# sch_the-weather-gian_2026-05-13.net
KiCad netlist of a schematic drawn in EasyEDA
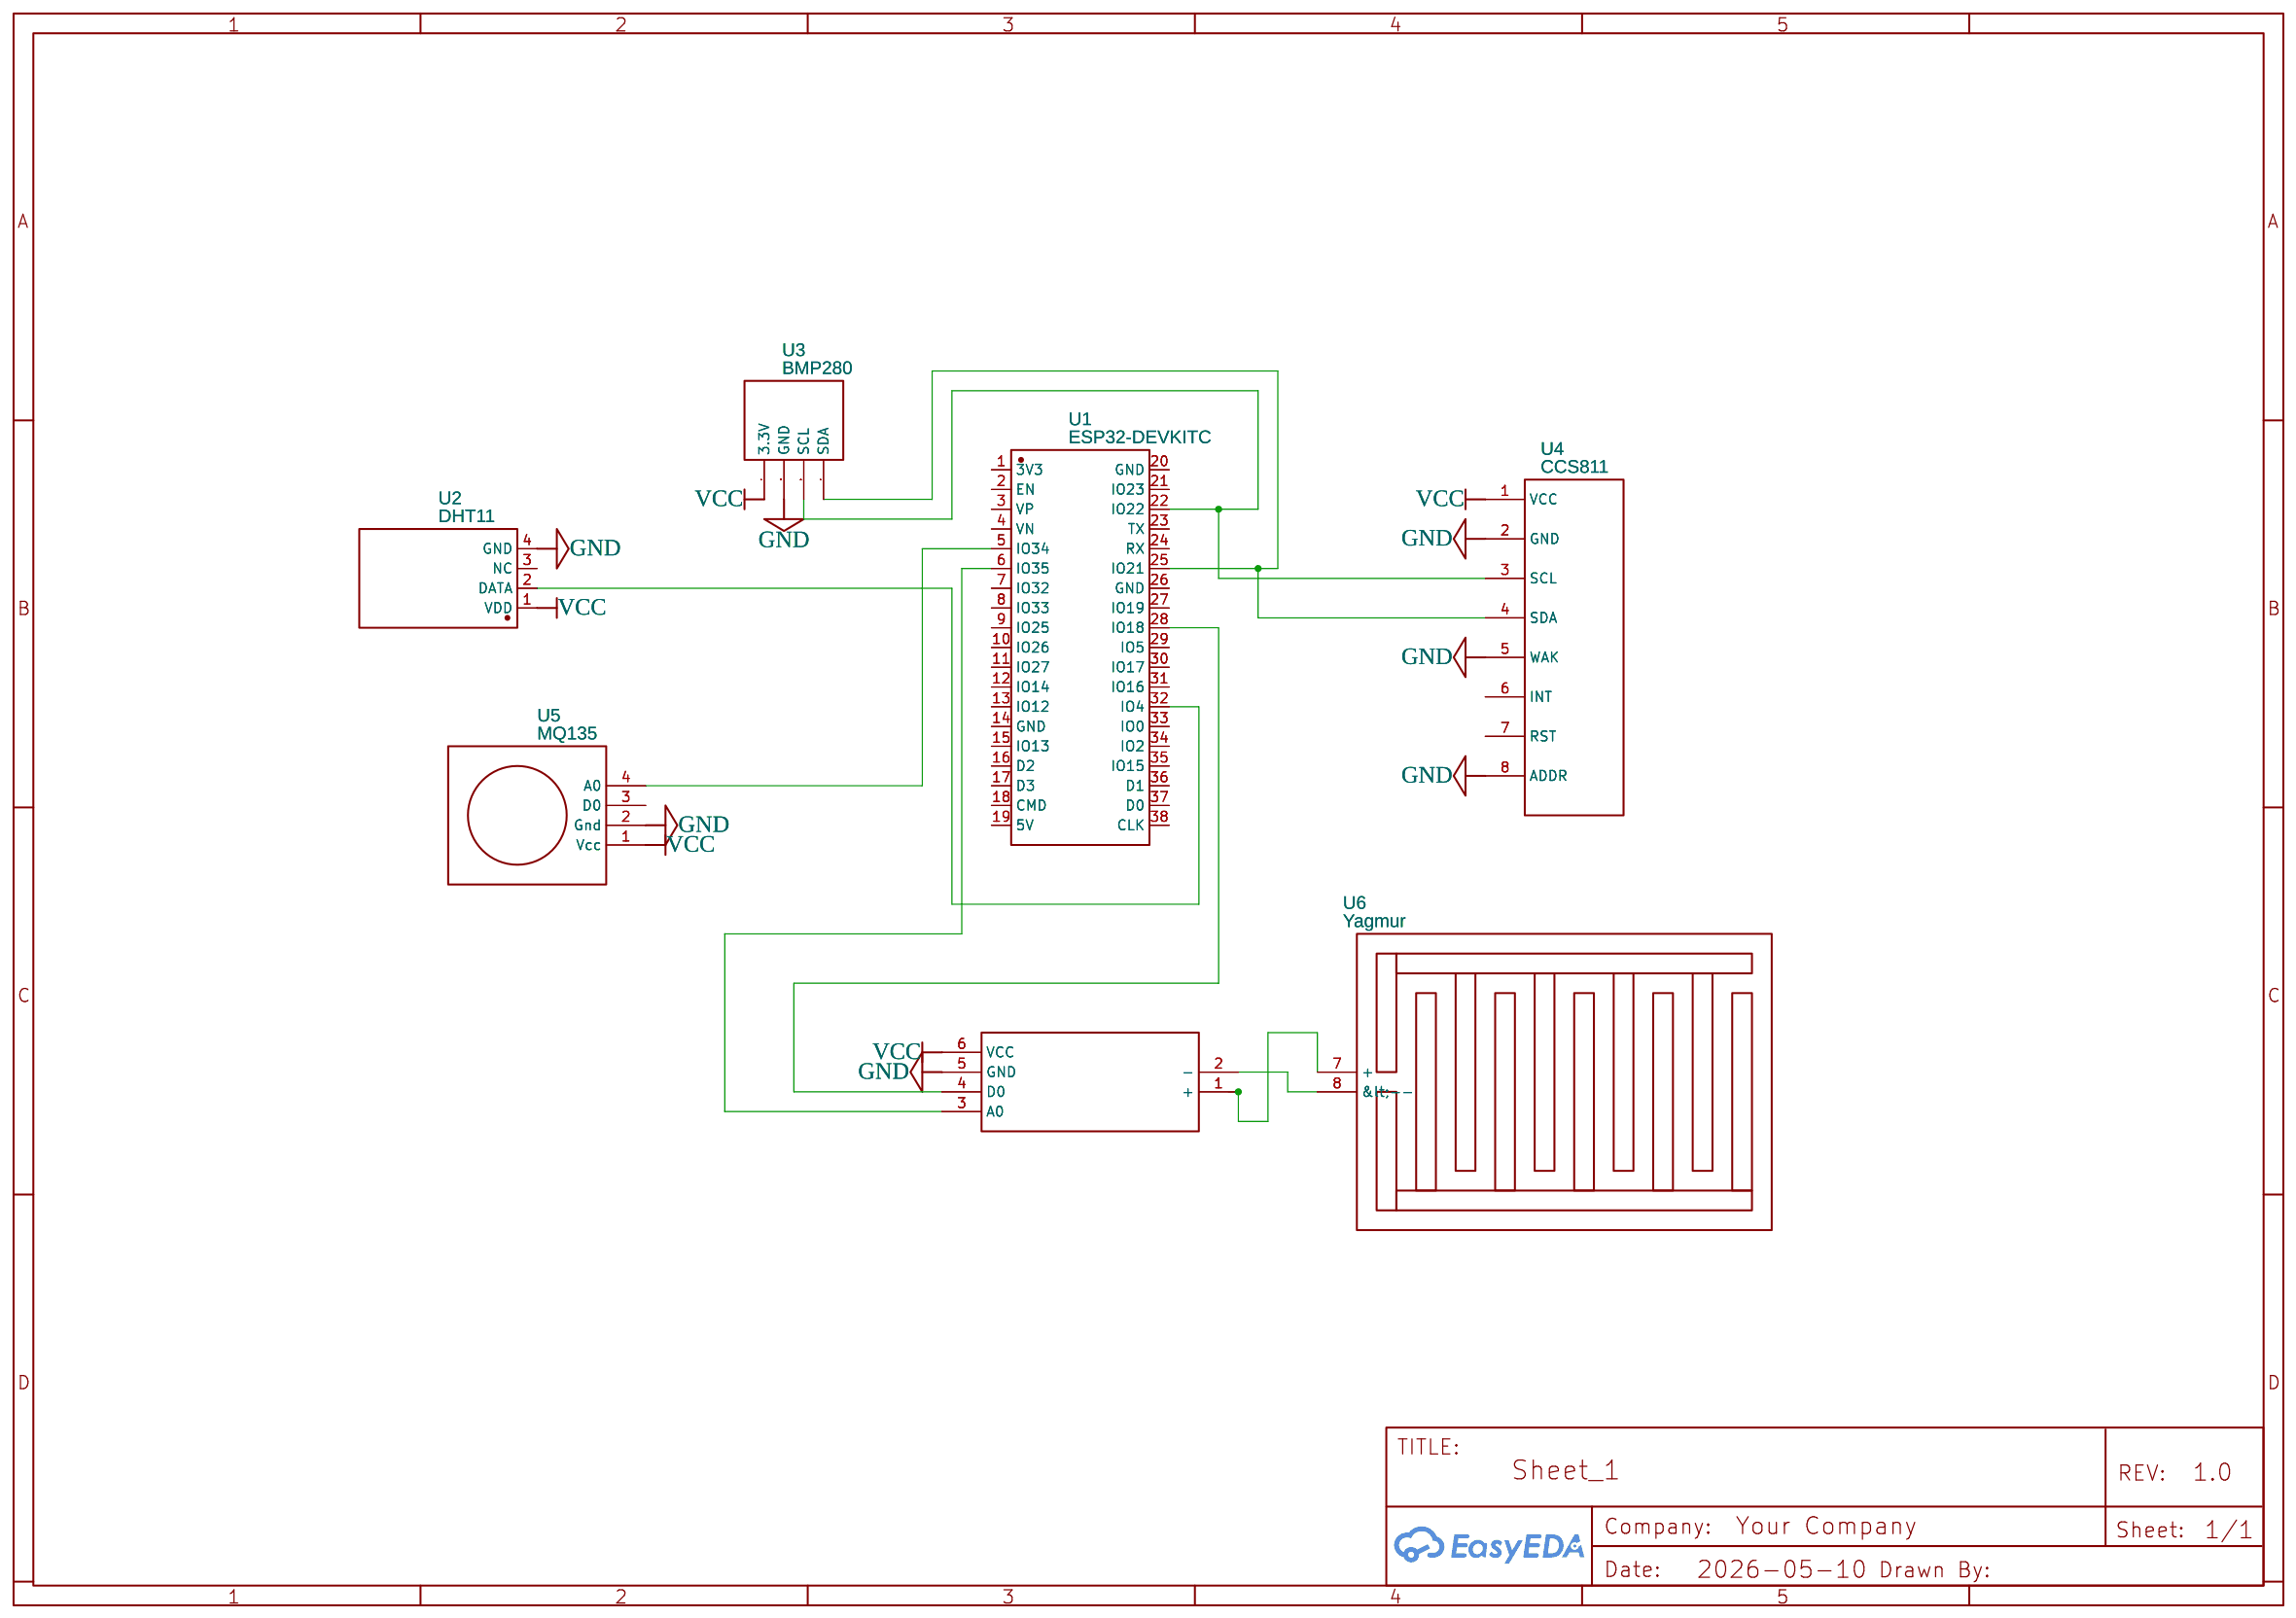
[diagram p0: schematic sheet]

(export (version "E")
  (design (tool "Eeschema 10.0.6"))
  (components
    (comp (ref "U1")
      (value "ESP32-DEVKITC")
      (fields
        (field (name "Manufacturer Part") "ESP32-DevKitC")
        (field (name "Manufacturer") "ESPRESSIF(乐鑫)")
      )
      (libsource (lib "") (part "ESP32-DEVKITC"))
    )
    (comp (ref "U2")
      (value "DHT11")
      (fields (field (name "Manufacturer") "广州奥松"))
      (libsource (lib "") (part "DHT11"))
    )
    (comp (ref "U3") (value "BMP280") (libsource (lib "") (part "BMP280")))
    (comp (ref "U4")
      (value "CCS811")
      (fields (field (name "Manufacturer Part") "CO2_SENS"))
      (libsource (lib "") (part "CCS811"))
    )
    (comp (ref "U5") (value "MQ135") (libsource (lib "") (part "MQ135")))
    (comp (ref "U6") (value "Yagmur") (libsource (lib "") (part "Yagmur")))
  )
  (nets
    (net (code "1") (name "GND") (class "Default")
      (node (ref "U2") (pin "4") (pinfunction "GND_4") (pintype "unspecified"))
      (node (ref "U3") (pin "6") (pinfunction "GND_6") (pintype "unspecified"))
      (node (ref "U4") (pin "2") (pinfunction "GND_2") (pintype "unspecified"))
      (node (ref "U4") (pin "5") (pinfunction "WAK_5") (pintype "unspecified"))
      (node (ref "U4") (pin "8") (pinfunction "ADDR_8") (pintype "unspecified"))
      (node (ref "U5") (pin "2") (pinfunction "Gnd_2") (pintype "unspecified"))
      (node (ref "U6") (pin "5") (pinfunction "GND_5") (pintype "unspecified"))
    )
    (net (code "2") (name "Net-(U1-IO4)") (class "Default")
      (node (ref "U1") (pin "32") (pinfunction "IO4_32") (pintype "unspecified"))
      (node (ref "U2") (pin "2") (pinfunction "DATA_2") (pintype "unspecified"))
    )
    (net (code "3") (name "Net-(U1-IO18)") (class "Default")
      (node (ref "U1") (pin "28") (pinfunction "IO18_28") (pintype "unspecified"))
      (node (ref "U6") (pin "4") (pinfunction "D0_4") (pintype "unspecified"))
    )
    (net (code "4") (name "Net-(U1-IO21)") (class "Default")
      (node (ref "U1") (pin "25") (pinfunction "IO21_25") (pintype "unspecified"))
      (node (ref "U3") (pin "4") (pinfunction "SDA_4") (pintype "unspecified"))
      (node (ref "U4") (pin "4") (pinfunction "SDA_4") (pintype "unspecified"))
    )
    (net (code "5") (name "Net-(U1-IO22)") (class "Default")
      (node (ref "U1") (pin "22") (pinfunction "IO22_22") (pintype "unspecified"))
      (node (ref "U3") (pin "5") (pinfunction "SCL_5") (pintype "unspecified"))
      (node (ref "U4") (pin "3") (pinfunction "SCL_3") (pintype "unspecified"))
    )
    (net (code "6") (name "Net-(U1-IO34)") (class "Default")
      (node (ref "U1") (pin "5") (pinfunction "IO34_5") (pintype "unspecified"))
      (node (ref "U5") (pin "4") (pinfunction "A0_4") (pintype "unspecified"))
    )
    (net (code "7") (name "Net-(U1-IO35)") (class "Default")
      (node (ref "U1") (pin "6") (pinfunction "IO35_6") (pintype "unspecified"))
      (node (ref "U6") (pin "3") (pinfunction "A0_3") (pintype "unspecified"))
    )
    (net (code "8") (name "Net-(U6-&lt;--)") (class "Default")
      (node (ref "U6") (pin "2") (pinfunction "-_2") (pintype "unspecified"))
      (node (ref "U6") (pin "8") (pinfunction "&lt;--_8") (pintype "unspecified"))
    )
    (net (code "9") (name "Net-(U6-+-Pad1)") (class "Default")
      (node (ref "U6") (pin "1") (pinfunction "+_1") (pintype "unspecified"))
      (node (ref "U6") (pin "7") (pinfunction "+_7") (pintype "unspecified"))
    )
    (net (code "10") (name "VCC") (class "Default")
      (node (ref "U2") (pin "1") (pinfunction "VDD_1") (pintype "unspecified"))
      (node (ref "U3") (pin "7") (pinfunction "3.3V_7") (pintype "unspecified"))
      (node (ref "U4") (pin "1") (pinfunction "VCC_1") (pintype "unspecified"))
      (node (ref "U5") (pin "1") (pinfunction "Vcc_1") (pintype "unspecified"))
      (node (ref "U6") (pin "6") (pinfunction "VCC_6") (pintype "unspecified"))
    )
    (net (code "11") (name "unconnected-(U1-3V3-Pad1)") (class "Default")
      (node (ref "U1") (pin "1") (pinfunction "3V3_1") (pintype "unspecified"))
    )
    (net (code "12") (name "unconnected-(U1-5V-Pad19)") (class "Default")
      (node (ref "U1") (pin "19") (pinfunction "5V_19") (pintype "unspecified"))
    )
    (net (code "13") (name "unconnected-(U1-CLK-Pad38)") (class "Default")
      (node (ref "U1") (pin "38") (pinfunction "CLK_38") (pintype "unspecified"))
    )
    (net (code "14") (name "unconnected-(U1-CMD-Pad18)") (class "Default")
      (node (ref "U1") (pin "18") (pinfunction "CMD_18") (pintype "unspecified"))
    )
    (net (code "15") (name "unconnected-(U1-D0-Pad37)") (class "Default")
      (node (ref "U1") (pin "37") (pinfunction "D0_37") (pintype "unspecified"))
    )
    (net (code "16") (name "unconnected-(U1-D1-Pad36)") (class "Default")
      (node (ref "U1") (pin "36") (pinfunction "D1_36") (pintype "unspecified"))
    )
    (net (code "17") (name "unconnected-(U1-D2-Pad16)") (class "Default")
      (node (ref "U1") (pin "16") (pinfunction "D2_16") (pintype "unspecified"))
    )
    (net (code "18") (name "unconnected-(U1-D3-Pad17)") (class "Default")
      (node (ref "U1") (pin "17") (pinfunction "D3_17") (pintype "unspecified"))
    )
    (net (code "19") (name "unconnected-(U1-EN-Pad2)") (class "Default")
      (node (ref "U1") (pin "2") (pinfunction "EN_2") (pintype "unspecified"))
    )
    (net (code "20") (name "unconnected-(U1-GND-Pad14)") (class "Default")
      (node (ref "U1") (pin "14") (pinfunction "GND_14") (pintype "unspecified"))
    )
    (net (code "21") (name "unconnected-(U1-GND-Pad20)") (class "Default")
      (node (ref "U1") (pin "20") (pinfunction "GND_20") (pintype "unspecified"))
    )
    (net (code "22") (name "unconnected-(U1-GND-Pad26)") (class "Default")
      (node (ref "U1") (pin "26") (pinfunction "GND_26") (pintype "unspecified"))
    )
    (net (code "23") (name "unconnected-(U1-IO0-Pad33)") (class "Default")
      (node (ref "U1") (pin "33") (pinfunction "IO0_33") (pintype "unspecified"))
    )
    (net (code "24") (name "unconnected-(U1-IO2-Pad34)") (class "Default")
      (node (ref "U1") (pin "34") (pinfunction "IO2_34") (pintype "unspecified"))
    )
    (net (code "25") (name "unconnected-(U1-IO5-Pad29)") (class "Default")
      (node (ref "U1") (pin "29") (pinfunction "IO5_29") (pintype "unspecified"))
    )
    (net (code "26") (name "unconnected-(U1-IO12-Pad13)") (class "Default")
      (node (ref "U1") (pin "13") (pinfunction "IO12_13") (pintype "unspecified"))
    )
    (net (code "27") (name "unconnected-(U1-IO13-Pad15)") (class "Default")
      (node (ref "U1") (pin "15") (pinfunction "IO13_15") (pintype "unspecified"))
    )
    (net (code "28") (name "unconnected-(U1-IO14-Pad12)") (class "Default")
      (node (ref "U1") (pin "12") (pinfunction "IO14_12") (pintype "unspecified"))
    )
    (net (code "29") (name "unconnected-(U1-IO15-Pad35)") (class "Default")
      (node (ref "U1") (pin "35") (pinfunction "IO15_35") (pintype "unspecified"))
    )
    (net (code "30") (name "unconnected-(U1-IO16-Pad31)") (class "Default")
      (node (ref "U1") (pin "31") (pinfunction "IO16_31") (pintype "unspecified"))
    )
    (net (code "31") (name "unconnected-(U1-IO17-Pad30)") (class "Default")
      (node (ref "U1") (pin "30") (pinfunction "IO17_30") (pintype "unspecified"))
    )
    (net (code "32") (name "unconnected-(U1-IO19-Pad27)") (class "Default")
      (node (ref "U1") (pin "27") (pinfunction "IO19_27") (pintype "unspecified"))
    )
    (net (code "33") (name "unconnected-(U1-IO23-Pad21)") (class "Default")
      (node (ref "U1") (pin "21") (pinfunction "IO23_21") (pintype "unspecified"))
    )
    (net (code "34") (name "unconnected-(U1-IO25-Pad9)") (class "Default")
      (node (ref "U1") (pin "9") (pinfunction "IO25_9") (pintype "unspecified"))
    )
    (net (code "35") (name "unconnected-(U1-IO26-Pad10)") (class "Default")
      (node (ref "U1") (pin "10") (pinfunction "IO26_10") (pintype "unspecified"))
    )
    (net (code "36") (name "unconnected-(U1-IO27-Pad11)") (class "Default")
      (node (ref "U1") (pin "11") (pinfunction "IO27_11") (pintype "unspecified"))
    )
    (net (code "37") (name "unconnected-(U1-IO32-Pad7)") (class "Default")
      (node (ref "U1") (pin "7") (pinfunction "IO32_7") (pintype "unspecified"))
    )
    (net (code "38") (name "unconnected-(U1-IO33-Pad8)") (class "Default")
      (node (ref "U1") (pin "8") (pinfunction "IO33_8") (pintype "unspecified"))
    )
    (net (code "39") (name "unconnected-(U1-RX-Pad24)") (class "Default")
      (node (ref "U1") (pin "24") (pinfunction "RX_24") (pintype "unspecified"))
    )
    (net (code "40") (name "unconnected-(U1-TX-Pad23)") (class "Default")
      (node (ref "U1") (pin "23") (pinfunction "TX_23") (pintype "unspecified"))
    )
    (net (code "41") (name "unconnected-(U1-VN-Pad4)") (class "Default")
      (node (ref "U1") (pin "4") (pinfunction "VN_4") (pintype "unspecified"))
    )
    (net (code "42") (name "unconnected-(U1-VP-Pad3)") (class "Default")
      (node (ref "U1") (pin "3") (pinfunction "VP_3") (pintype "unspecified"))
    )
    (net (code "43") (name "unconnected-(U2-NC-Pad3)") (class "Default")
      (node (ref "U2") (pin "3") (pinfunction "NC_3") (pintype "unspecified"))
    )
    (net (code "44") (name "unconnected-(U4-INT-Pad6)") (class "Default")
      (node (ref "U4") (pin "6") (pinfunction "INT_6") (pintype "unspecified"))
    )
    (net (code "45") (name "unconnected-(U4-RST-Pad7)") (class "Default")
      (node (ref "U4") (pin "7") (pinfunction "RST_7") (pintype "unspecified"))
    )
    (net (code "46") (name "unconnected-(U5-D0-Pad3)") (class "Default")
      (node (ref "U5") (pin "3") (pinfunction "D0_3") (pintype "unspecified"))
    )
  )
)
